# FANET_RPiZero.net
KiCad netlist of a schematic drawn in EAGLE
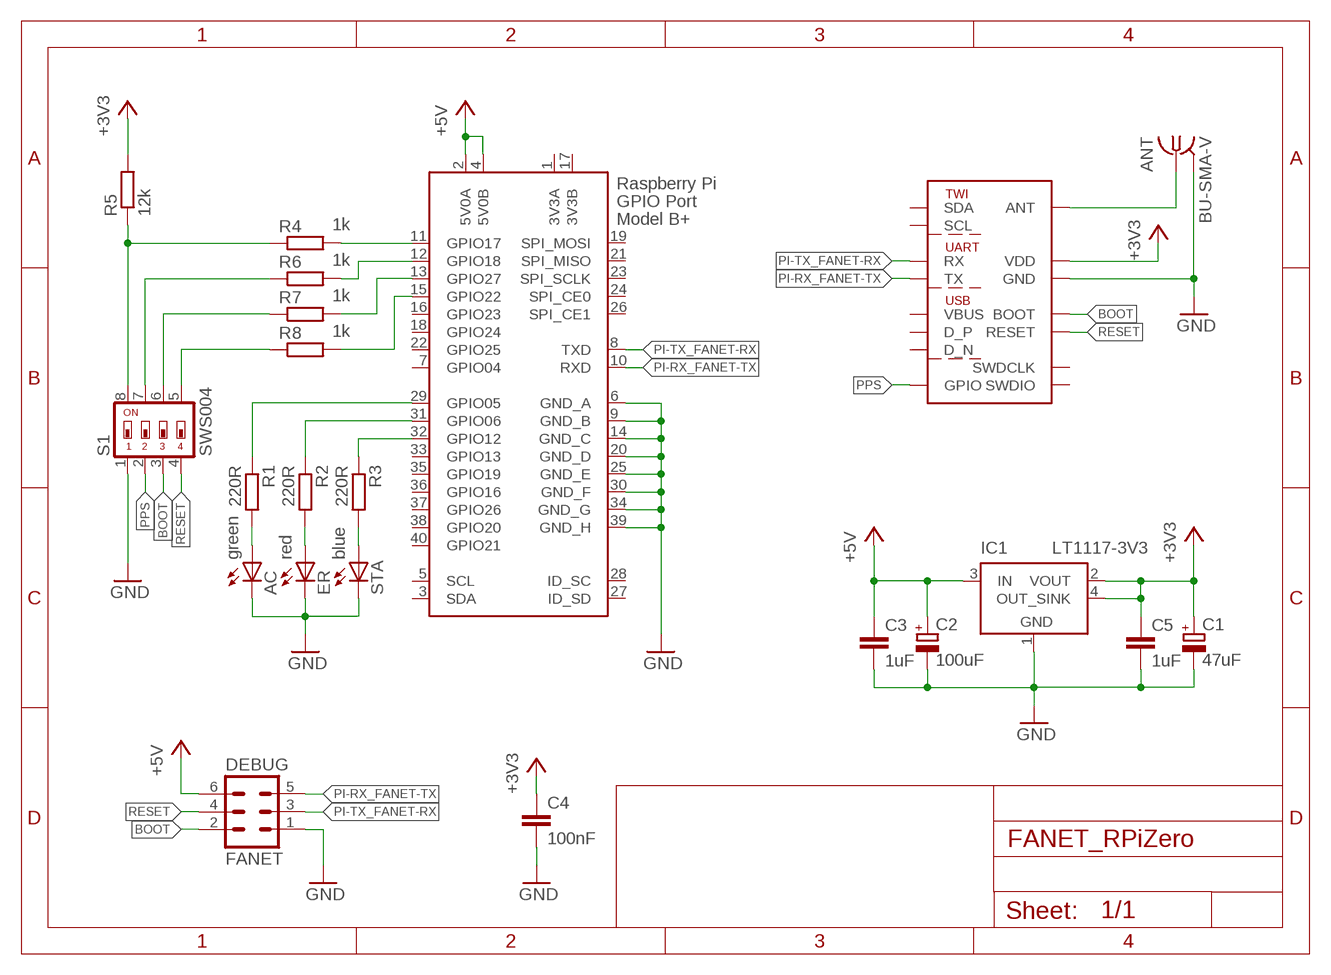
[diagram p0: schematic, sheet 1]

(export (version "E")
  (design (tool "Eeschema 10.0.6"))
  (components
    (comp (ref "AC")
      (value "green")
      (footprint "eagle-import:CHIP-LED0805")
      (libsource (lib "eagle-import") (part "LEDCHIP-LED0805"))
    )
    (comp (ref "ANT")
      (value "BU-SMA-V")
      (footprint "eagle-import:BU-SMA-V")
      (libsource (lib "eagle-import") (part "BU-SMA-V"))
    )
    (comp (ref "C1")
      (value "47uF")
      (footprint "eagle-import:SMC_C")
      (libsource (lib "eagle-import") (part "CPOL-EUSMCC"))
    )
    (comp (ref "C2")
      (value "100uF")
      (footprint "eagle-import:SMC_C")
      (libsource (lib "eagle-import") (part "CPOL-EUSMCC"))
    )
    (comp (ref "C3")
      (value "1uF")
      (footprint "eagle-import:C1206")
      (libsource (lib "eagle-import") (part "C-EUC1206"))
    )
    (comp (ref "C4")
      (value "100nF")
      (footprint "eagle-import:C1206")
      (libsource (lib "eagle-import") (part "C-EUC1206"))
    )
    (comp (ref "C5")
      (value "1uF")
      (footprint "eagle-import:C1206")
      (libsource (lib "eagle-import") (part "C-EUC1206"))
    )
    (comp (ref "DEBUG")
      (value "FANET")
      (footprint "eagle-import:ML6")
      (libsource (lib "eagle-import") (part "ML6"))
    )
    (comp (ref "ER")
      (value "red")
      (footprint "eagle-import:CHIP-LED0805")
      (libsource (lib "eagle-import") (part "LEDCHIP-LED0805"))
    )
    (comp (ref "FANET_MODULE")
      (value "FANET_MODULE")
      (footprint "eagle-import:FANET_INTERNAL")
      (libsource (lib "eagle-import") (part "FANET_MODULE"))
    )
    (comp (ref "IC1")
      (value "LT1117-3V3")
      (footprint "eagle-import:SOT223")
      (fields (field (name "MPN") "LT1117"))
      (libsource (lib "eagle-import") (part "LT1117"))
    )
    (comp (ref "R1")
      (value "220R")
      (footprint "eagle-import:R0805")
      (libsource (lib "eagle-import") (part "R-EU_R0805"))
    )
    (comp (ref "R2")
      (value "220R")
      (footprint "eagle-import:R0805")
      (libsource (lib "eagle-import") (part "R-EU_R0805"))
    )
    (comp (ref "R3")
      (value "220R")
      (footprint "eagle-import:R0805")
      (libsource (lib "eagle-import") (part "R-EU_R0805"))
    )
    (comp (ref "R4")
      (value "1k")
      (footprint "eagle-import:R0805")
      (libsource (lib "eagle-import") (part "R-EU_R0805"))
    )
    (comp (ref "R5")
      (value "12k")
      (footprint "eagle-import:R0805")
      (libsource (lib "eagle-import") (part "R-EU_R0805"))
    )
    (comp (ref "R6")
      (value "1k")
      (footprint "eagle-import:R0805")
      (libsource (lib "eagle-import") (part "R-EU_R0805"))
    )
    (comp (ref "R7")
      (value "1k")
      (footprint "eagle-import:R0805")
      (libsource (lib "eagle-import") (part "R-EU_R0805"))
    )
    (comp (ref "R8")
      (value "1k")
      (footprint "eagle-import:R0805")
      (libsource (lib "eagle-import") (part "R-EU_R0805"))
    )
    (comp (ref "RASPI_ZERO")
      (value "RASPI_GPIO_B+#")
      (footprint "eagle-import:RASPI_BOARD_ZERO_FULL_PAD")
      (libsource (lib "eagle-import") (part "RASPI_GPIO_B+#"))
    )
    (comp (ref "S1")
      (value "SWS004")
      (footprint "eagle-import:SMS-004")
      (libsource (lib "eagle-import") (part "SWS004"))
    )
    (comp (ref "STA")
      (value "blue")
      (footprint "eagle-import:CHIP-LED0805")
      (libsource (lib "eagle-import") (part "LEDCHIP-LED0805"))
    )
  )
  (nets
    (net (code "1") (name "+3V3") (class "Default")
      (node (ref "C1") (pin "+") (pinfunction "+_+") (pintype "passive"))
      (node (ref "C4") (pin "1") (pinfunction "1_1") (pintype "passive"))
      (node (ref "C5") (pin "1") (pinfunction "1_1") (pintype "passive"))
      (node (ref "FANET_MODULE") (pin "VSS") (pinfunction "VDD_VSS") (pintype "bidirectional"))
      (node (ref "IC1") (pin "2") (pinfunction "VOUT_2") (pintype "passive"))
      (node (ref "IC1") (pin "4") (pinfunction "OUT_SINK_4") (pintype "passive"))
      (node (ref "R5") (pin "2") (pinfunction "2_2") (pintype "passive"))
    )
    (net (code "2") (name "+5V") (class "Default")
      (node (ref "C2") (pin "+") (pinfunction "+_+") (pintype "passive"))
      (node (ref "C3") (pin "1") (pinfunction "1_1") (pintype "passive"))
      (node (ref "DEBUG") (pin "6") (pinfunction "6_6") (pintype "passive"))
      (node (ref "IC1") (pin "3") (pinfunction "IN_3") (pintype "input"))
      (node (ref "RASPI_ZERO") (pin "2") (pinfunction "5V0A_2") (pintype "power_in"))
      (node (ref "RASPI_ZERO") (pin "4") (pinfunction "5V0B_4") (pintype "power_in"))
    )
    (net (code "3") (name "/3V3A") (class "Default")
      (node (ref "RASPI_ZERO") (pin "1") (pinfunction "3V3A_1") (pintype "power_in"))
    )
    (net (code "4") (name "/3V3B") (class "Default")
      (node (ref "RASPI_ZERO") (pin "17") (pinfunction "3V3B_17") (pintype "power_in"))
    )
    (net (code "5") (name "BOOT") (class "Default")
      (node (ref "DEBUG") (pin "2") (pinfunction "2_2") (pintype "passive"))
      (node (ref "FANET_MODULE") (pin "BOOT") (pinfunction "BOOT_BOOT") (pintype "bidirectional"))
      (node (ref "S1") (pin "3") (pinfunction "3_3") (pintype "passive"))
    )
    (net (code "6") (name "GND") (class "Default")
      (node (ref "AC") (pin "C") (pinfunction "C_C") (pintype "passive"))
      (node (ref "ANT") (pin "2") (pinfunction "2_2") (pintype "passive"))
      (node (ref "ANT") (pin "3") (pinfunction "2_3") (pintype "passive"))
      (node (ref "ANT") (pin "4") (pinfunction "2_4") (pintype "passive"))
      (node (ref "ANT") (pin "5") (pinfunction "2_5") (pintype "passive"))
      (node (ref "C1") (pin "-") (pinfunction "-_-") (pintype "passive"))
      (node (ref "C2") (pin "-") (pinfunction "-_-") (pintype "passive"))
      (node (ref "C3") (pin "2") (pinfunction "2_2") (pintype "passive"))
      (node (ref "C4") (pin "2") (pinfunction "2_2") (pintype "passive"))
      (node (ref "C5") (pin "2") (pinfunction "2_2") (pintype "passive"))
      (node (ref "DEBUG") (pin "1") (pinfunction "1_1") (pintype "passive"))
      (node (ref "ER") (pin "C") (pinfunction "C_C") (pintype "passive"))
      (node (ref "FANET_MODULE") (pin "GND0") (pinfunction "GND_GND0") (pintype "bidirectional"))
      (node (ref "FANET_MODULE") (pin "GND1") (pinfunction "GND_GND1") (pintype "bidirectional"))
      (node (ref "IC1") (pin "1") (pinfunction "GND_1") (pintype "power_in"))
      (node (ref "RASPI_ZERO") (pin "14") (pinfunction "GND_C_14") (pintype "power_in"))
      (node (ref "RASPI_ZERO") (pin "20") (pinfunction "GND_D_20") (pintype "power_in"))
      (node (ref "RASPI_ZERO") (pin "25") (pinfunction "GND_E_25") (pintype "power_in"))
      (node (ref "RASPI_ZERO") (pin "30") (pinfunction "GND_F_30") (pintype "power_in"))
      (node (ref "RASPI_ZERO") (pin "34") (pinfunction "GND_G_34") (pintype "power_in"))
      (node (ref "RASPI_ZERO") (pin "39") (pinfunction "GND_H_39") (pintype "power_in"))
      (node (ref "RASPI_ZERO") (pin "6") (pinfunction "GND_A_6") (pintype "power_in"))
      (node (ref "RASPI_ZERO") (pin "9") (pinfunction "GND_B_9") (pintype "power_in"))
      (node (ref "S1") (pin "1") (pinfunction "1_1") (pintype "passive"))
      (node (ref "STA") (pin "C") (pinfunction "C_C") (pintype "passive"))
    )
    (net (code "7") (name "Net-(AC-PadA)") (class "Default")
      (node (ref "AC") (pin "A") (pinfunction "A_A") (pintype "passive"))
      (node (ref "R1") (pin "2") (pinfunction "2_2") (pintype "passive"))
    )
    (net (code "8") (name "Net-(ANT-Pad1)") (class "Default")
      (node (ref "ANT") (pin "1") (pinfunction "1_1") (pintype "passive"))
      (node (ref "FANET_MODULE") (pin "ANT") (pinfunction "ANT_ANT") (pintype "bidirectional"))
    )
    (net (code "9") (name "Net-(ER-PadA)") (class "Default")
      (node (ref "ER") (pin "A") (pinfunction "A_A") (pintype "passive"))
      (node (ref "R2") (pin "2") (pinfunction "2_2") (pintype "passive"))
    )
    (net (code "10") (name "Net-(R3-Pad2)") (class "Default")
      (node (ref "R3") (pin "2") (pinfunction "2_2") (pintype "passive"))
      (node (ref "STA") (pin "A") (pinfunction "A_A") (pintype "passive"))
    )
    (net (code "11") (name "Net-(R4-Pad1)") (class "Default")
      (node (ref "R4") (pin "1") (pinfunction "1_1") (pintype "passive"))
      (node (ref "R5") (pin "1") (pinfunction "1_1") (pintype "passive"))
      (node (ref "S1") (pin "8") (pinfunction "8_8") (pintype "passive"))
    )
    (net (code "12") (name "Net-(R6-Pad1)") (class "Default")
      (node (ref "R6") (pin "1") (pinfunction "1_1") (pintype "passive"))
      (node (ref "S1") (pin "7") (pinfunction "7_7") (pintype "passive"))
    )
    (net (code "13") (name "Net-(R7-Pad1)") (class "Default")
      (node (ref "R7") (pin "1") (pinfunction "1_1") (pintype "passive"))
      (node (ref "S1") (pin "6") (pinfunction "6_6") (pintype "passive"))
    )
    (net (code "14") (name "Net-(R8-Pad1)") (class "Default")
      (node (ref "R8") (pin "1") (pinfunction "1_1") (pintype "passive"))
      (node (ref "S1") (pin "5") (pinfunction "5_5") (pintype "passive"))
    )
    (net (code "15") (name "Net-(RASPI_ZERO-GPIO05)") (class "Default")
      (node (ref "R1") (pin "1") (pinfunction "1_1") (pintype "passive"))
      (node (ref "RASPI_ZERO") (pin "29") (pinfunction "GPIO05_29") (pintype "bidirectional"))
    )
    (net (code "16") (name "Net-(RASPI_ZERO-GPIO06)") (class "Default")
      (node (ref "R2") (pin "1") (pinfunction "1_1") (pintype "passive"))
      (node (ref "RASPI_ZERO") (pin "31") (pinfunction "GPIO06_31") (pintype "bidirectional"))
    )
    (net (code "17") (name "Net-(RASPI_ZERO-GPIO12)") (class "Default")
      (node (ref "R3") (pin "1") (pinfunction "1_1") (pintype "passive"))
      (node (ref "RASPI_ZERO") (pin "32") (pinfunction "GPIO12_32") (pintype "bidirectional"))
    )
    (net (code "18") (name "Net-(RASPI_ZERO-GPIO17)") (class "Default")
      (node (ref "R4") (pin "2") (pinfunction "2_2") (pintype "passive"))
      (node (ref "RASPI_ZERO") (pin "11") (pinfunction "GPIO17_11") (pintype "bidirectional"))
    )
    (net (code "19") (name "Net-(RASPI_ZERO-GPIO18)") (class "Default")
      (node (ref "R6") (pin "2") (pinfunction "2_2") (pintype "passive"))
      (node (ref "RASPI_ZERO") (pin "12") (pinfunction "GPIO18_12") (pintype "bidirectional"))
    )
    (net (code "20") (name "Net-(RASPI_ZERO-GPIO22)") (class "Default")
      (node (ref "R8") (pin "2") (pinfunction "2_2") (pintype "passive"))
      (node (ref "RASPI_ZERO") (pin "15") (pinfunction "GPIO22_15") (pintype "bidirectional"))
    )
    (net (code "21") (name "Net-(RASPI_ZERO-GPIO27)") (class "Default")
      (node (ref "R7") (pin "2") (pinfunction "2_2") (pintype "passive"))
      (node (ref "RASPI_ZERO") (pin "13") (pinfunction "GPIO27_13") (pintype "bidirectional"))
    )
    (net (code "22") (name "PI-RX_FANET-TX") (class "Default")
      (node (ref "DEBUG") (pin "5") (pinfunction "5_5") (pintype "passive"))
      (node (ref "FANET_MODULE") (pin "TX") (pinfunction "TX_TX") (pintype "bidirectional"))
      (node (ref "RASPI_ZERO") (pin "10") (pinfunction "RXD_10") (pintype "input"))
    )
    (net (code "23") (name "PI-TX_FANET-RX") (class "Default")
      (node (ref "DEBUG") (pin "3") (pinfunction "3_3") (pintype "passive"))
      (node (ref "FANET_MODULE") (pin "RX") (pinfunction "RX_RX") (pintype "bidirectional"))
      (node (ref "RASPI_ZERO") (pin "8") (pinfunction "TXD_8") (pintype "output"))
    )
    (net (code "24") (name "PPS") (class "Default")
      (node (ref "FANET_MODULE") (pin "GPIO0") (pinfunction "GPIO_GPIO0") (pintype "bidirectional"))
      (node (ref "S1") (pin "2") (pinfunction "2_2") (pintype "passive"))
    )
    (net (code "25") (name "RESET") (class "Default")
      (node (ref "DEBUG") (pin "4") (pinfunction "4_4") (pintype "passive"))
      (node (ref "FANET_MODULE") (pin "RESET") (pinfunction "RESET_RESET") (pintype "bidirectional"))
      (node (ref "S1") (pin "4") (pinfunction "4_4") (pintype "passive"))
    )
    (net (code "26") (name "unconnected-(FANET_MODULE-PadD_N)") (class "Default")
      (node (ref "FANET_MODULE") (pin "D_N") (pinfunction "D_N_D_N") (pintype "bidirectional"))
    )
    (net (code "27") (name "unconnected-(FANET_MODULE-PadD_P)") (class "Default")
      (node (ref "FANET_MODULE") (pin "D_P") (pinfunction "D_P_D_P") (pintype "bidirectional"))
    )
    (net (code "28") (name "unconnected-(FANET_MODULE-PadSCL)") (class "Default")
      (node (ref "FANET_MODULE") (pin "SCL") (pinfunction "SCL_SCL") (pintype "bidirectional"))
    )
    (net (code "29") (name "unconnected-(FANET_MODULE-PadSDA)") (class "Default")
      (node (ref "FANET_MODULE") (pin "SDA") (pinfunction "SDA_SDA") (pintype "bidirectional"))
    )
    (net (code "30") (name "unconnected-(FANET_MODULE-PadSWDCLK)") (class "Default")
      (node (ref "FANET_MODULE") (pin "SWDCLK") (pinfunction "SWDCLK_SWDCLK") (pintype "bidirectional"))
    )
    (net (code "31") (name "unconnected-(FANET_MODULE-PadSWDIO)") (class "Default")
      (node (ref "FANET_MODULE") (pin "SWDIO") (pinfunction "SWDIO_SWDIO") (pintype "bidirectional"))
    )
    (net (code "32") (name "unconnected-(FANET_MODULE-PadVBUS)") (class "Default")
      (node (ref "FANET_MODULE") (pin "VBUS") (pinfunction "VBUS_VBUS") (pintype "bidirectional"))
    )
    (net (code "33") (name "unconnected-(RASPI_ZERO-GPIO04-Pad7)") (class "Default")
      (node (ref "RASPI_ZERO") (pin "7") (pinfunction "GPIO04_7") (pintype "bidirectional"))
    )
    (net (code "34") (name "unconnected-(RASPI_ZERO-GPIO13-Pad33)") (class "Default")
      (node (ref "RASPI_ZERO") (pin "33") (pinfunction "GPIO13_33") (pintype "bidirectional"))
    )
    (net (code "35") (name "unconnected-(RASPI_ZERO-GPIO16-Pad36)") (class "Default")
      (node (ref "RASPI_ZERO") (pin "36") (pinfunction "GPIO16_36") (pintype "bidirectional"))
    )
    (net (code "36") (name "unconnected-(RASPI_ZERO-GPIO19-Pad35)") (class "Default")
      (node (ref "RASPI_ZERO") (pin "35") (pinfunction "GPIO19_35") (pintype "bidirectional"))
    )
    (net (code "37") (name "unconnected-(RASPI_ZERO-GPIO20-Pad38)") (class "Default")
      (node (ref "RASPI_ZERO") (pin "38") (pinfunction "GPIO20_38") (pintype "bidirectional"))
    )
    (net (code "38") (name "unconnected-(RASPI_ZERO-GPIO21-Pad40)") (class "Default")
      (node (ref "RASPI_ZERO") (pin "40") (pinfunction "GPIO21_40") (pintype "bidirectional"))
    )
    (net (code "39") (name "unconnected-(RASPI_ZERO-GPIO23-Pad16)") (class "Default")
      (node (ref "RASPI_ZERO") (pin "16") (pinfunction "GPIO23_16") (pintype "bidirectional"))
    )
    (net (code "40") (name "unconnected-(RASPI_ZERO-GPIO24-Pad18)") (class "Default")
      (node (ref "RASPI_ZERO") (pin "18") (pinfunction "GPIO24_18") (pintype "bidirectional"))
    )
    (net (code "41") (name "unconnected-(RASPI_ZERO-GPIO25-Pad22)") (class "Default")
      (node (ref "RASPI_ZERO") (pin "22") (pinfunction "GPIO25_22") (pintype "bidirectional"))
    )
    (net (code "42") (name "unconnected-(RASPI_ZERO-GPIO26-Pad37)") (class "Default")
      (node (ref "RASPI_ZERO") (pin "37") (pinfunction "GPIO26_37") (pintype "bidirectional"))
    )
    (net (code "43") (name "unconnected-(RASPI_ZERO-ID_SC-Pad28)") (class "Default")
      (node (ref "RASPI_ZERO") (pin "28") (pinfunction "ID_SC_28") (pintype "no_connect"))
    )
    (net (code "44") (name "unconnected-(RASPI_ZERO-ID_SD-Pad27)") (class "Default")
      (node (ref "RASPI_ZERO") (pin "27") (pinfunction "ID_SD_27") (pintype "no_connect"))
    )
    (net (code "45") (name "unconnected-(RASPI_ZERO-SCL-Pad5)") (class "Default")
      (node (ref "RASPI_ZERO") (pin "5") (pinfunction "SCL_5") (pintype "bidirectional"))
    )
    (net (code "46") (name "unconnected-(RASPI_ZERO-SDA-Pad3)") (class "Default")
      (node (ref "RASPI_ZERO") (pin "3") (pinfunction "SDA_3") (pintype "bidirectional"))
    )
    (net (code "47") (name "unconnected-(RASPI_ZERO-SPI_CE0-Pad24)") (class "Default")
      (node (ref "RASPI_ZERO") (pin "24") (pinfunction "SPI_CE0_24") (pintype "bidirectional"))
    )
    (net (code "48") (name "unconnected-(RASPI_ZERO-SPI_CE1-Pad26)") (class "Default")
      (node (ref "RASPI_ZERO") (pin "26") (pinfunction "SPI_CE1_26") (pintype "bidirectional"))
    )
    (net (code "49") (name "unconnected-(RASPI_ZERO-SPI_MISO-Pad21)") (class "Default")
      (node (ref "RASPI_ZERO") (pin "21") (pinfunction "SPI_MISO_21") (pintype "bidirectional"))
    )
    (net (code "50") (name "unconnected-(RASPI_ZERO-SPI_MOSI-Pad19)") (class "Default")
      (node (ref "RASPI_ZERO") (pin "19") (pinfunction "SPI_MOSI_19") (pintype "bidirectional"))
    )
    (net (code "51") (name "unconnected-(RASPI_ZERO-SPI_SCLK-Pad23)") (class "Default")
      (node (ref "RASPI_ZERO") (pin "23") (pinfunction "SPI_SCLK_23") (pintype "bidirectional"))
    )
  )
)
